# 4_waffling60-MX_periferals.net
KiCad netlist of a schematic drawn in Altium Designer
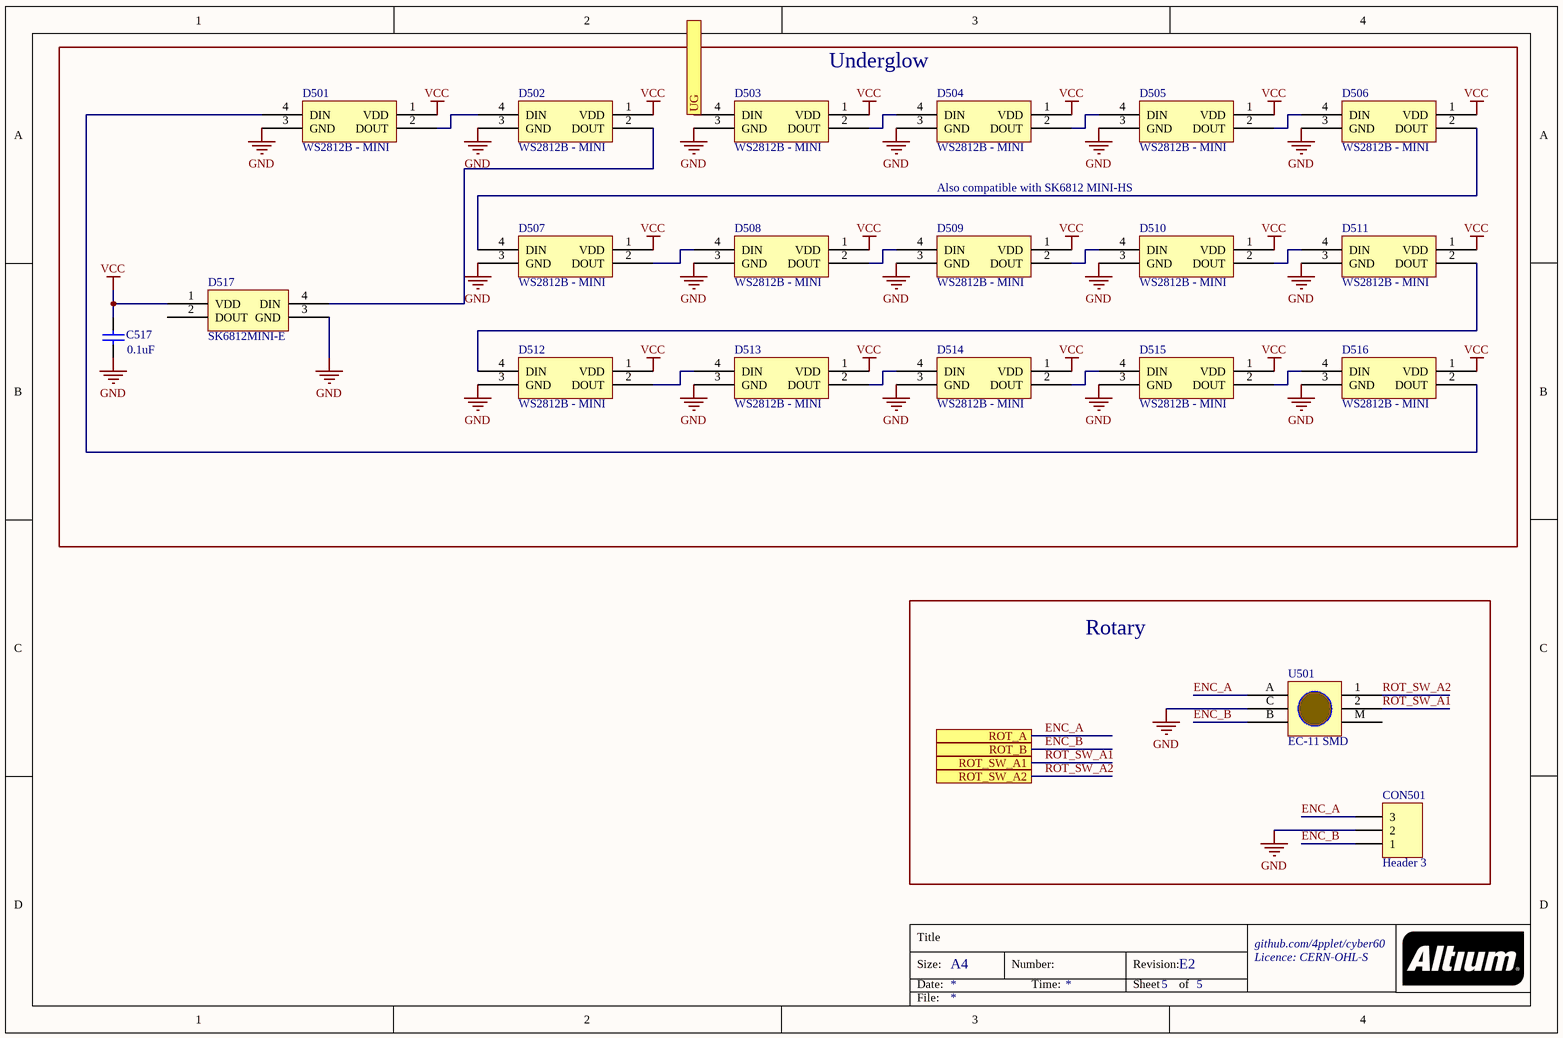
[diagram p0: 4_waffling60-MX_periferals.SchDoc]

(export (version "E")
  (design (tool "Eeschema 10.0.6"))
  (components
    (comp (ref "C517")
      (value "0.1uF")
      (footprint "C0603[1608]")
      (description "Capacitor")
      (fields (field (name "LCSC PART #") "C14663") (field (name "MRF.PART") "CC0603KRX7R9BB104"))
      (libsource (lib "Miscellaneous Devices") (part "Cap"))
    )
    (comp (ref "CON501")
      (value "Header 3")
      (footprint "HDR1X3")
      (description "Header, 3-Pin")
      (libsource (lib "Miscellaneous Connectors") (part "Header 3"))
    )
    (comp (ref "D501")
      (value "WS2812B - MINI")
      (footprint "WS2812B - 2020")
      (fields (field (name "LCSC PART #") "C965555") (field (name "MRF.PART") "WS2812B-2020"))
      (libsource (lib "Keebs") (part "WS2812B"))
    )
    (comp (ref "D502")
      (value "WS2812B - MINI")
      (footprint "WS2812B - 2020")
      (fields (field (name "LCSC PART #") "C965555") (field (name "MRF.PART") "WS2812B-2020"))
      (libsource (lib "Keebs") (part "WS2812B"))
    )
    (comp (ref "D503")
      (value "WS2812B - MINI")
      (footprint "WS2812B - 2020")
      (fields (field (name "LCSC PART #") "C965555") (field (name "MRF.PART") "WS2812B-2020"))
      (libsource (lib "Keebs") (part "WS2812B"))
    )
    (comp (ref "D504")
      (value "WS2812B - MINI")
      (footprint "WS2812B - 2020")
      (fields (field (name "LCSC PART #") "C965555") (field (name "MRF.PART") "WS2812B-2020"))
      (libsource (lib "Keebs") (part "WS2812B"))
    )
    (comp (ref "D505")
      (value "WS2812B - MINI")
      (footprint "WS2812B - 2020")
      (fields (field (name "LCSC PART #") "C965555") (field (name "MRF.PART") "WS2812B-2020"))
      (libsource (lib "Keebs") (part "WS2812B"))
    )
    (comp (ref "D506")
      (value "WS2812B - MINI")
      (footprint "WS2812B - 2020")
      (fields (field (name "LCSC PART #") "C965555") (field (name "MRF.PART") "WS2812B-2020"))
      (libsource (lib "Keebs") (part "WS2812B"))
    )
    (comp (ref "D507")
      (value "WS2812B - MINI")
      (footprint "WS2812B - 2020")
      (fields (field (name "LCSC PART #") "C965555") (field (name "MRF.PART") "WS2812B-2020"))
      (libsource (lib "Keebs") (part "WS2812B"))
    )
    (comp (ref "D508")
      (value "WS2812B - MINI")
      (footprint "WS2812B - 2020")
      (fields (field (name "LCSC PART #") "C965555") (field (name "MRF.PART") "WS2812B-2020"))
      (libsource (lib "Keebs") (part "WS2812B"))
    )
    (comp (ref "D509")
      (value "WS2812B - MINI")
      (footprint "WS2812B - 2020")
      (fields (field (name "LCSC PART #") "C965555") (field (name "MRF.PART") "WS2812B-2020"))
      (libsource (lib "Keebs") (part "WS2812B"))
    )
    (comp (ref "D510")
      (value "WS2812B - MINI")
      (footprint "WS2812B - 2020")
      (fields (field (name "LCSC PART #") "C965555") (field (name "MRF.PART") "WS2812B-2020"))
      (libsource (lib "Keebs") (part "WS2812B"))
    )
    (comp (ref "D511")
      (value "WS2812B - MINI")
      (footprint "WS2812B - 2020")
      (fields (field (name "LCSC PART #") "C965555") (field (name "MRF.PART") "WS2812B-2020"))
      (libsource (lib "Keebs") (part "WS2812B"))
    )
    (comp (ref "D512")
      (value "WS2812B - MINI")
      (footprint "WS2812B - 2020")
      (fields (field (name "LCSC PART #") "C965555") (field (name "MRF.PART") "WS2812B-2020"))
      (libsource (lib "Keebs") (part "WS2812B"))
    )
    (comp (ref "D513")
      (value "WS2812B - MINI")
      (footprint "WS2812B - 2020")
      (fields (field (name "LCSC PART #") "C965555") (field (name "MRF.PART") "WS2812B-2020"))
      (libsource (lib "Keebs") (part "WS2812B"))
    )
    (comp (ref "D514")
      (value "WS2812B - MINI")
      (footprint "WS2812B - 2020")
      (fields (field (name "LCSC PART #") "C965555") (field (name "MRF.PART") "WS2812B-2020"))
      (libsource (lib "Keebs") (part "WS2812B"))
    )
    (comp (ref "D515")
      (value "WS2812B - MINI")
      (footprint "WS2812B - 2020")
      (fields (field (name "LCSC PART #") "C965555") (field (name "MRF.PART") "WS2812B-2020"))
      (libsource (lib "Keebs") (part "WS2812B"))
    )
    (comp (ref "D516")
      (value "WS2812B - MINI")
      (footprint "WS2812B - 2020")
      (fields (field (name "LCSC PART #") "C965555") (field (name "MRF.PART") "WS2812B-2020"))
      (libsource (lib "Keebs") (part "WS2812B"))
    )
    (comp (ref "D517")
      (value "SK6812MINI-E")
      (footprint "SK6812MINI-E - shaped")
      (fields (field (name "LCSC PART #") "C524051") (field (name "MRF.PART") "DY-S352818/RGBC/6812-2T"))
      (libsource (lib "Keebs") (part "SK6812MINI-E"))
    )
    (comp (ref "U501") (value "EC-11 SMD") (footprint "EC11-SMD") (libsource (lib "Keebs") (part "EC-11")))
  )
  (nets
    (net (code "1") (name "/ENC_A") (class "Default")
      (node (ref "CON501") (pin "3") (pinfunction "3_3") (pintype "passive"))
      (node (ref "U501") (pin "A") (pinfunction "B_A") (pintype "passive"))
    )
    (net (code "2") (name "/ENC_B") (class "Default")
      (node (ref "CON501") (pin "1") (pinfunction "1_1") (pintype "passive"))
      (node (ref "U501") (pin "B") (pinfunction "B_B") (pintype "passive"))
    )
    (net (code "3") (name "/ROT_SW_A1") (class "Default")
      (node (ref "U501") (pin "2") (pinfunction "2_2") (pintype "passive"))
    )
    (net (code "4") (name "/ROT_SW_A2") (class "Default")
      (node (ref "U501") (pin "1") (pinfunction "1_1") (pintype "passive"))
    )
    (net (code "5") (name "/UG") (class "Default")
      (node (ref "D503") (pin "4") (pinfunction "DIN_4") (pintype "passive"))
    )
    (net (code "6") (name "GND") (class "Default")
      (node (ref "C517") (pin "1") (pinfunction "1_1") (pintype "passive"))
      (node (ref "CON501") (pin "2") (pinfunction "2_2") (pintype "passive"))
      (node (ref "D501") (pin "3") (pinfunction "GND_3") (pintype "passive"))
      (node (ref "D502") (pin "3") (pinfunction "GND_3") (pintype "passive"))
      (node (ref "D503") (pin "3") (pinfunction "GND_3") (pintype "passive"))
      (node (ref "D504") (pin "3") (pinfunction "GND_3") (pintype "passive"))
      (node (ref "D505") (pin "3") (pinfunction "GND_3") (pintype "passive"))
      (node (ref "D506") (pin "3") (pinfunction "GND_3") (pintype "passive"))
      (node (ref "D507") (pin "3") (pinfunction "GND_3") (pintype "passive"))
      (node (ref "D508") (pin "3") (pinfunction "GND_3") (pintype "passive"))
      (node (ref "D509") (pin "3") (pinfunction "GND_3") (pintype "passive"))
      (node (ref "D510") (pin "3") (pinfunction "GND_3") (pintype "passive"))
      (node (ref "D511") (pin "3") (pinfunction "GND_3") (pintype "passive"))
      (node (ref "D512") (pin "3") (pinfunction "GND_3") (pintype "passive"))
      (node (ref "D513") (pin "3") (pinfunction "GND_3") (pintype "passive"))
      (node (ref "D514") (pin "3") (pinfunction "GND_3") (pintype "passive"))
      (node (ref "D515") (pin "3") (pinfunction "GND_3") (pintype "passive"))
      (node (ref "D516") (pin "3") (pinfunction "GND_3") (pintype "passive"))
      (node (ref "D517") (pin "3") (pinfunction "GND_3") (pintype "passive"))
      (node (ref "U501") (pin "C") (pinfunction "C_C") (pintype "passive"))
    )
    (net (code "7") (name "Net-(D501-DIN)") (class "Default")
      (node (ref "D501") (pin "4") (pinfunction "DIN_4") (pintype "passive"))
      (node (ref "D516") (pin "2") (pinfunction "DOUT_2") (pintype "passive"))
    )
    (net (code "8") (name "Net-(D501-DOUT)") (class "Default")
      (node (ref "D501") (pin "2") (pinfunction "DOUT_2") (pintype "passive"))
      (node (ref "D502") (pin "4") (pinfunction "DIN_4") (pintype "passive"))
    )
    (net (code "9") (name "Net-(D502-DOUT)") (class "Default")
      (node (ref "D502") (pin "2") (pinfunction "DOUT_2") (pintype "passive"))
      (node (ref "D517") (pin "4") (pinfunction "DIN_4") (pintype "passive"))
    )
    (net (code "10") (name "Net-(D503-DOUT)") (class "Default")
      (node (ref "D503") (pin "2") (pinfunction "DOUT_2") (pintype "passive"))
      (node (ref "D504") (pin "4") (pinfunction "DIN_4") (pintype "passive"))
    )
    (net (code "11") (name "Net-(D504-DOUT)") (class "Default")
      (node (ref "D504") (pin "2") (pinfunction "DOUT_2") (pintype "passive"))
      (node (ref "D505") (pin "4") (pinfunction "DIN_4") (pintype "passive"))
    )
    (net (code "12") (name "Net-(D505-DOUT)") (class "Default")
      (node (ref "D505") (pin "2") (pinfunction "DOUT_2") (pintype "passive"))
      (node (ref "D506") (pin "4") (pinfunction "DIN_4") (pintype "passive"))
    )
    (net (code "13") (name "Net-(D506-DOUT)") (class "Default")
      (node (ref "D506") (pin "2") (pinfunction "DOUT_2") (pintype "passive"))
      (node (ref "D507") (pin "4") (pinfunction "DIN_4") (pintype "passive"))
    )
    (net (code "14") (name "Net-(D507-DOUT)") (class "Default")
      (node (ref "D507") (pin "2") (pinfunction "DOUT_2") (pintype "passive"))
      (node (ref "D508") (pin "4") (pinfunction "DIN_4") (pintype "passive"))
    )
    (net (code "15") (name "Net-(D508-DOUT)") (class "Default")
      (node (ref "D508") (pin "2") (pinfunction "DOUT_2") (pintype "passive"))
      (node (ref "D509") (pin "4") (pinfunction "DIN_4") (pintype "passive"))
    )
    (net (code "16") (name "Net-(D509-DOUT)") (class "Default")
      (node (ref "D509") (pin "2") (pinfunction "DOUT_2") (pintype "passive"))
      (node (ref "D510") (pin "4") (pinfunction "DIN_4") (pintype "passive"))
    )
    (net (code "17") (name "Net-(D510-DOUT)") (class "Default")
      (node (ref "D510") (pin "2") (pinfunction "DOUT_2") (pintype "passive"))
      (node (ref "D511") (pin "4") (pinfunction "DIN_4") (pintype "passive"))
    )
    (net (code "18") (name "Net-(D511-DOUT)") (class "Default")
      (node (ref "D511") (pin "2") (pinfunction "DOUT_2") (pintype "passive"))
      (node (ref "D512") (pin "4") (pinfunction "DIN_4") (pintype "passive"))
    )
    (net (code "19") (name "Net-(D512-DOUT)") (class "Default")
      (node (ref "D512") (pin "2") (pinfunction "DOUT_2") (pintype "passive"))
      (node (ref "D513") (pin "4") (pinfunction "DIN_4") (pintype "passive"))
    )
    (net (code "20") (name "Net-(D513-DOUT)") (class "Default")
      (node (ref "D513") (pin "2") (pinfunction "DOUT_2") (pintype "passive"))
      (node (ref "D514") (pin "4") (pinfunction "DIN_4") (pintype "passive"))
    )
    (net (code "21") (name "Net-(D514-DOUT)") (class "Default")
      (node (ref "D514") (pin "2") (pinfunction "DOUT_2") (pintype "passive"))
      (node (ref "D515") (pin "4") (pinfunction "DIN_4") (pintype "passive"))
    )
    (net (code "22") (name "Net-(D515-DOUT)") (class "Default")
      (node (ref "D515") (pin "2") (pinfunction "DOUT_2") (pintype "passive"))
      (node (ref "D516") (pin "4") (pinfunction "DIN_4") (pintype "passive"))
    )
    (net (code "23") (name "VCC") (class "Default")
      (node (ref "C517") (pin "2") (pinfunction "2_2") (pintype "passive"))
      (node (ref "D501") (pin "1") (pinfunction "VDD_1") (pintype "passive"))
      (node (ref "D502") (pin "1") (pinfunction "VDD_1") (pintype "passive"))
      (node (ref "D503") (pin "1") (pinfunction "VDD_1") (pintype "passive"))
      (node (ref "D504") (pin "1") (pinfunction "VDD_1") (pintype "passive"))
      (node (ref "D505") (pin "1") (pinfunction "VDD_1") (pintype "passive"))
      (node (ref "D506") (pin "1") (pinfunction "VDD_1") (pintype "passive"))
      (node (ref "D507") (pin "1") (pinfunction "VDD_1") (pintype "passive"))
      (node (ref "D508") (pin "1") (pinfunction "VDD_1") (pintype "passive"))
      (node (ref "D509") (pin "1") (pinfunction "VDD_1") (pintype "passive"))
      (node (ref "D510") (pin "1") (pinfunction "VDD_1") (pintype "passive"))
      (node (ref "D511") (pin "1") (pinfunction "VDD_1") (pintype "passive"))
      (node (ref "D512") (pin "1") (pinfunction "VDD_1") (pintype "passive"))
      (node (ref "D513") (pin "1") (pinfunction "VDD_1") (pintype "passive"))
      (node (ref "D514") (pin "1") (pinfunction "VDD_1") (pintype "passive"))
      (node (ref "D515") (pin "1") (pinfunction "VDD_1") (pintype "passive"))
      (node (ref "D516") (pin "1") (pinfunction "VDD_1") (pintype "passive"))
      (node (ref "D517") (pin "1") (pinfunction "VDD_1") (pintype "passive"))
    )
    (net (code "24") (name "unconnected-(D517-DOUT-Pad2)") (class "Default")
      (node (ref "D517") (pin "2") (pinfunction "DOUT_2") (pintype "passive"))
    )
    (net (code "25") (name "unconnected-(U501-PadM)") (class "Default")
      (node (ref "U501") (pin "M") (pinfunction "M_M") (pintype "passive"))
    )
  )
)
